# CCM_0025.net
KiCad netlist of a schematic drawn in EAGLE
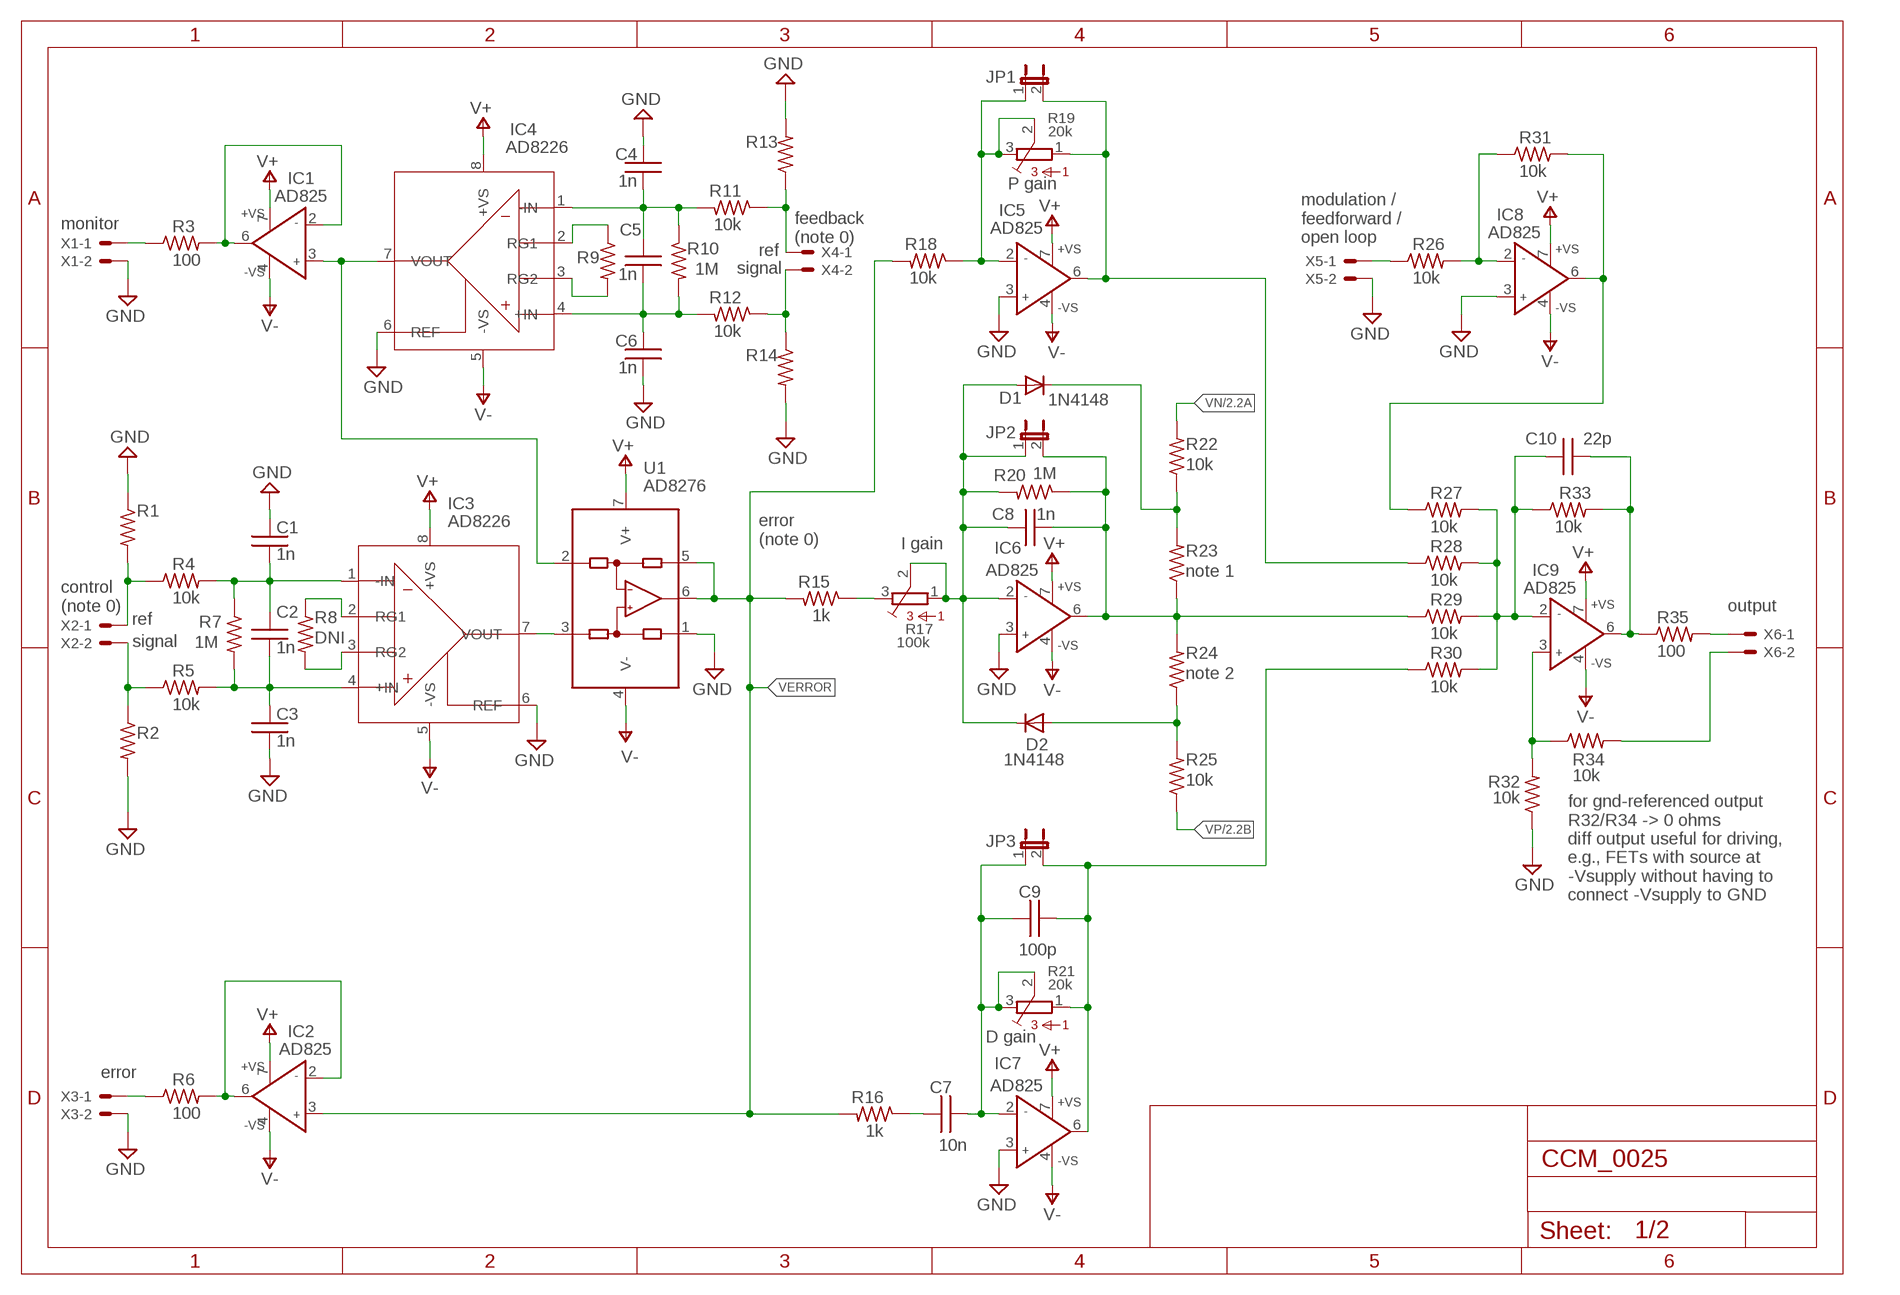
[diagram p0: schematic, sheet 1]
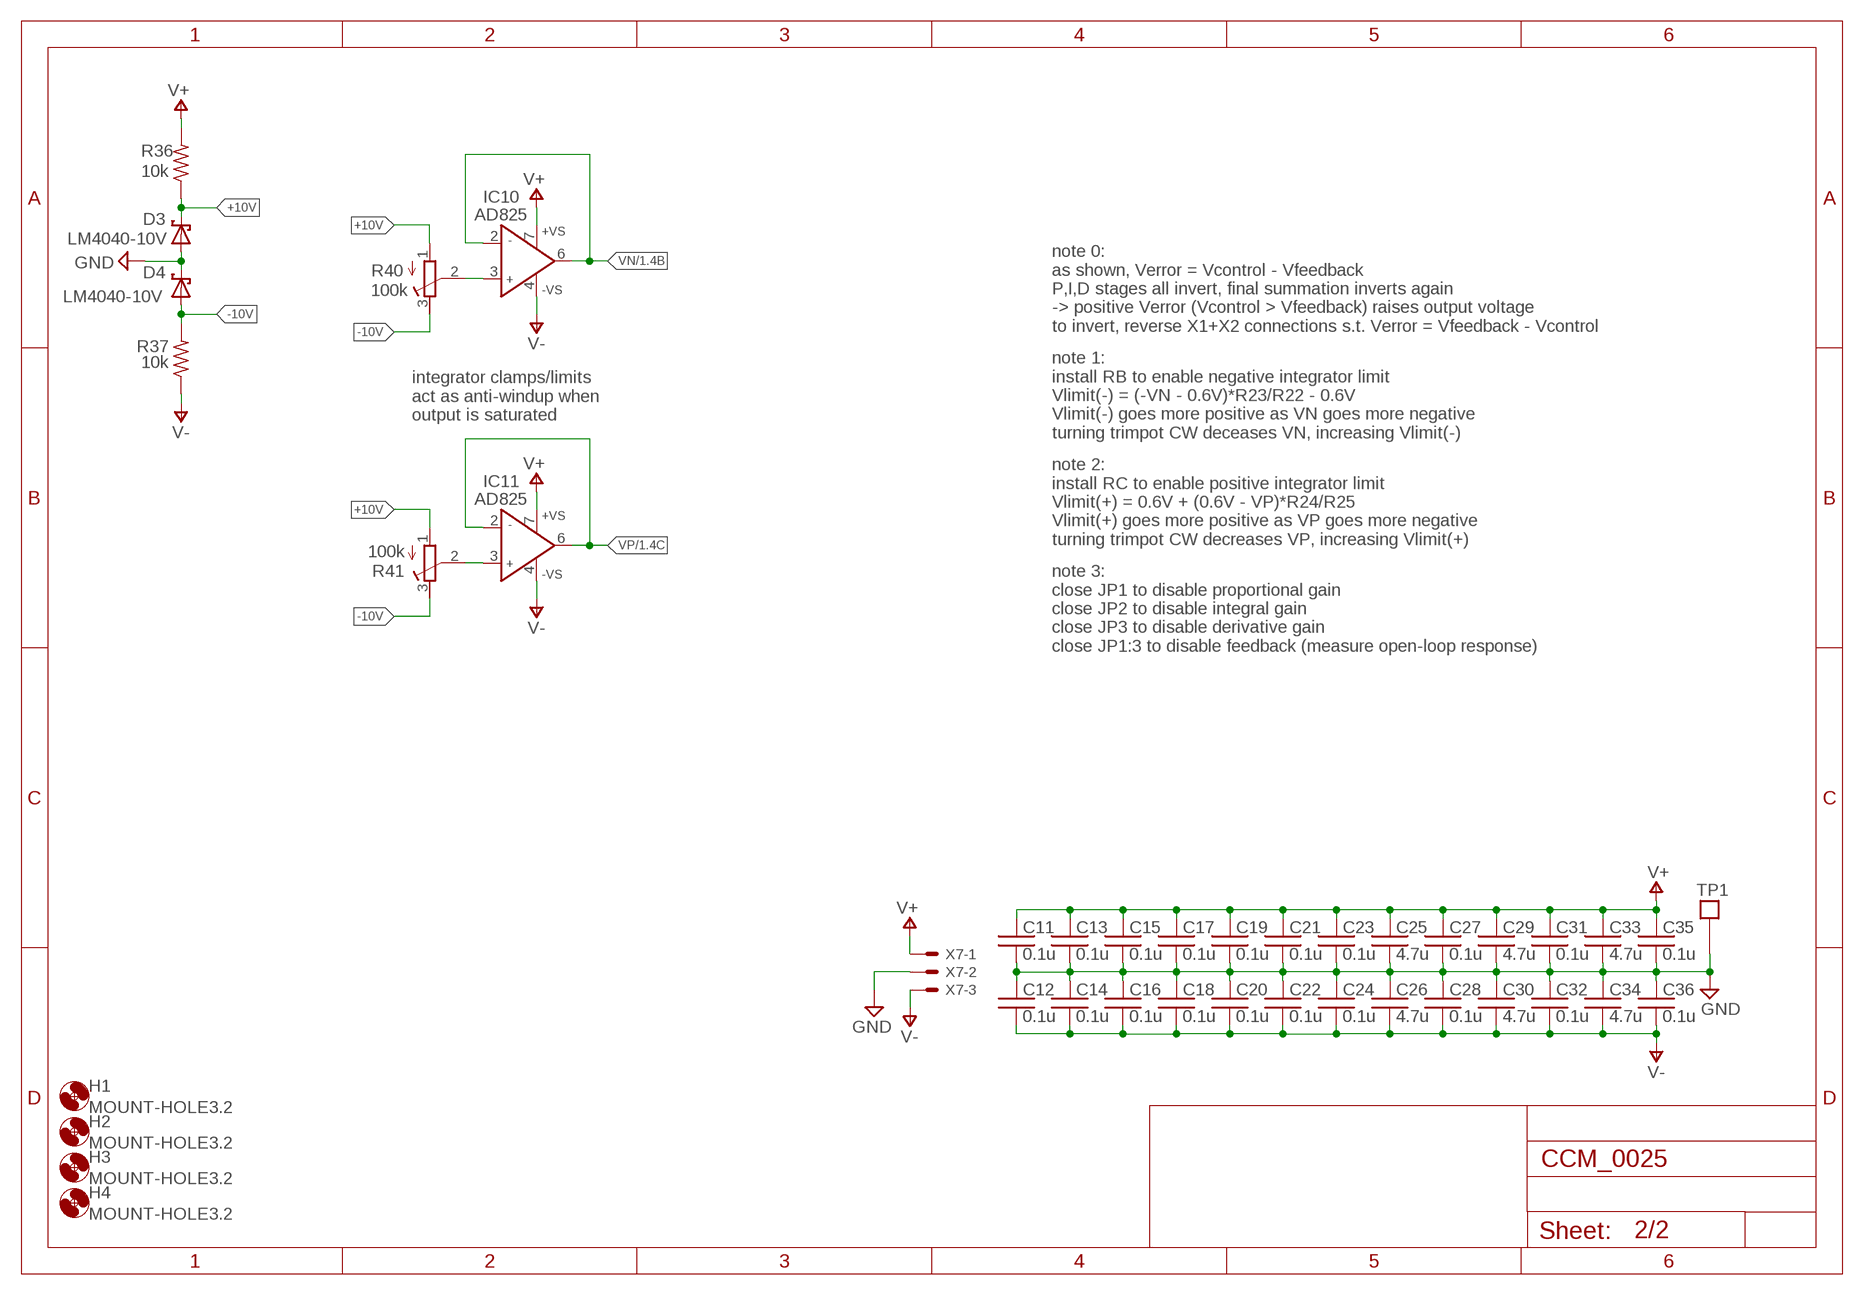
[diagram p1: schematic, sheet 2]

(export (version "E")
  (design (tool "Eeschema 10.0.6"))
  (components
    (comp (ref "C1")
      (value "1n")
      (footprint "eagle-import:0603")
      (libsource (lib "eagle-import") (part "C0603"))
    )
    (comp (ref "C2")
      (value "1n")
      (footprint "eagle-import:0603")
      (libsource (lib "eagle-import") (part "C0603"))
    )
    (comp (ref "C3")
      (value "1n")
      (footprint "eagle-import:0603")
      (libsource (lib "eagle-import") (part "C0603"))
    )
    (comp (ref "C4")
      (value "1n")
      (footprint "eagle-import:0603")
      (libsource (lib "eagle-import") (part "C0603"))
    )
    (comp (ref "C5")
      (value "1n")
      (footprint "eagle-import:0603")
      (libsource (lib "eagle-import") (part "C0603"))
    )
    (comp (ref "C6")
      (value "1n")
      (footprint "eagle-import:0603")
      (libsource (lib "eagle-import") (part "C0603"))
    )
    (comp (ref "C7")
      (value "10n")
      (footprint "eagle-import:0603")
      (libsource (lib "eagle-import") (part "C0603"))
    )
    (comp (ref "C8")
      (value "1n")
      (footprint "eagle-import:0603")
      (libsource (lib "eagle-import") (part "C0603"))
    )
    (comp (ref "C9")
      (value "100p")
      (footprint "eagle-import:0603")
      (libsource (lib "eagle-import") (part "C0603"))
    )
    (comp (ref "C10")
      (value "22p")
      (footprint "eagle-import:0603")
      (libsource (lib "eagle-import") (part "C0603"))
    )
    (comp (ref "D1")
      (value "1N4148")
      (footprint "eagle-import:SOD323_ST")
      (libsource (lib "eagle-import") (part "1N4148"))
    )
    (comp (ref "D2")
      (value "1N4148")
      (footprint "eagle-import:SOD323_ST")
      (libsource (lib "eagle-import") (part "1N4148"))
    )
    (comp (ref "IC1")
      (value "AD825")
      (footprint "eagle-import:SO8")
      (fields (field (name "MF") "ALTERA CORPORATION") (field (name "MPN") "AD825ARZ"))
      (libsource (lib "eagle-import") (part "AD825_BR"))
    )
    (comp (ref "IC2")
      (value "AD825")
      (footprint "eagle-import:SO8")
      (fields (field (name "MF") "ALTERA CORPORATION") (field (name "MPN") "AD825ARZ"))
      (libsource (lib "eagle-import") (part "AD825_BR"))
    )
    (comp (ref "IC3")
      (value "AD8226")
      (footprint "eagle-import:SO08")
      (libsource (lib "eagle-import") (part "AD8226"))
    )
    (comp (ref "IC4")
      (value "AD8226")
      (footprint "eagle-import:SO08")
      (libsource (lib "eagle-import") (part "AD8226"))
    )
    (comp (ref "IC5")
      (value "AD825")
      (footprint "eagle-import:SO8")
      (fields (field (name "MF") "ALTERA CORPORATION") (field (name "MPN") "AD825ARZ"))
      (libsource (lib "eagle-import") (part "AD825_BR"))
    )
    (comp (ref "IC6")
      (value "AD825")
      (footprint "eagle-import:SO8")
      (fields (field (name "MF") "ALTERA CORPORATION") (field (name "MPN") "AD825ARZ"))
      (libsource (lib "eagle-import") (part "AD825_BR"))
    )
    (comp (ref "IC7")
      (value "AD825")
      (footprint "eagle-import:SO8")
      (fields (field (name "MF") "ALTERA CORPORATION") (field (name "MPN") "AD825ARZ"))
      (libsource (lib "eagle-import") (part "AD825_BR"))
    )
    (comp (ref "IC8")
      (value "AD825")
      (footprint "eagle-import:SO8")
      (fields (field (name "MF") "ALTERA CORPORATION") (field (name "MPN") "AD825ARZ"))
      (libsource (lib "eagle-import") (part "AD825_BR"))
    )
    (comp (ref "IC9")
      (value "AD825")
      (footprint "eagle-import:SO8")
      (fields (field (name "MF") "ALTERA CORPORATION") (field (name "MPN") "AD825ARZ"))
      (libsource (lib "eagle-import") (part "AD825_BR"))
    )
    (comp (ref "JP1")
      (value "JP1E")
      (footprint "eagle-import:JP1")
      (libsource (lib "eagle-import") (part "JP1E"))
    )
    (comp (ref "JP2")
      (value "JP1E")
      (footprint "eagle-import:JP1")
      (libsource (lib "eagle-import") (part "JP1E"))
    )
    (comp (ref "JP3")
      (value "JP1E")
      (footprint "eagle-import:JP1")
      (libsource (lib "eagle-import") (part "JP1E"))
    )
    (comp (ref "R1")
      (value "10k")
      (footprint "eagle-import:0603")
      (libsource (lib "eagle-import") (part "R0603"))
    )
    (comp (ref "R2")
      (value "10k")
      (footprint "eagle-import:0603")
      (libsource (lib "eagle-import") (part "R0603"))
    )
    (comp (ref "R3")
      (value "100")
      (footprint "eagle-import:0603")
      (libsource (lib "eagle-import") (part "R0603"))
    )
    (comp (ref "R4")
      (value "10k")
      (footprint "eagle-import:0603")
      (libsource (lib "eagle-import") (part "R0603"))
    )
    (comp (ref "R5")
      (value "10k")
      (footprint "eagle-import:0603")
      (libsource (lib "eagle-import") (part "R0603"))
    )
    (comp (ref "R6")
      (value "100")
      (footprint "eagle-import:0603")
      (libsource (lib "eagle-import") (part "R0603"))
    )
    (comp (ref "R7")
      (value "1M")
      (footprint "eagle-import:0603")
      (libsource (lib "eagle-import") (part "R0603"))
    )
    (comp (ref "R8")
      (value "DNI")
      (footprint "eagle-import:0603")
      (libsource (lib "eagle-import") (part "R0603"))
    )
    (comp (ref "R9")
      (value "DNI")
      (footprint "eagle-import:0603")
      (libsource (lib "eagle-import") (part "R0603"))
    )
    (comp (ref "R10")
      (value "1M")
      (footprint "eagle-import:0603")
      (libsource (lib "eagle-import") (part "R0603"))
    )
    (comp (ref "R11")
      (value "10k")
      (footprint "eagle-import:0603")
      (libsource (lib "eagle-import") (part "R0603"))
    )
    (comp (ref "R12")
      (value "10k")
      (footprint "eagle-import:0603")
      (libsource (lib "eagle-import") (part "R0603"))
    )
    (comp (ref "R13")
      (value "10k")
      (footprint "eagle-import:0603")
      (libsource (lib "eagle-import") (part "R0603"))
    )
    (comp (ref "R14")
      (value "10k")
      (footprint "eagle-import:0603")
      (libsource (lib "eagle-import") (part "R0603"))
    )
    (comp (ref "R15")
      (value "1k")
      (footprint "eagle-import:0603")
      (libsource (lib "eagle-import") (part "R0603"))
    )
    (comp (ref "R16")
      (value "1k")
      (footprint "eagle-import:0603")
      (libsource (lib "eagle-import") (part "R0603"))
    )
    (comp (ref "R17")
      (value "100k")
      (footprint "eagle-import:3386C")
      (libsource (lib "eagle-import") (part "3386-C"))
    )
    (comp (ref "R18")
      (value "10k")
      (footprint "eagle-import:0603")
      (libsource (lib "eagle-import") (part "R0603"))
    )
    (comp (ref "R19")
      (value "20k")
      (footprint "eagle-import:3386C")
      (libsource (lib "eagle-import") (part "3386-C"))
    )
    (comp (ref "R20")
      (value "1M")
      (footprint "eagle-import:0603")
      (libsource (lib "eagle-import") (part "R0603"))
    )
    (comp (ref "R21")
      (value "20k")
      (footprint "eagle-import:3386C")
      (libsource (lib "eagle-import") (part "3386-C"))
    )
    (comp (ref "R22")
      (value "10k")
      (footprint "eagle-import:0603")
      (libsource (lib "eagle-import") (part "R0603"))
    )
    (comp (ref "R23")
      (value "note 1")
      (footprint "eagle-import:0603")
      (libsource (lib "eagle-import") (part "R0603"))
    )
    (comp (ref "R24")
      (value "note 2")
      (footprint "eagle-import:0603")
      (libsource (lib "eagle-import") (part "R0603"))
    )
    (comp (ref "R25")
      (value "10k")
      (footprint "eagle-import:0603")
      (libsource (lib "eagle-import") (part "R0603"))
    )
    (comp (ref "R26")
      (value "10k")
      (footprint "eagle-import:0603")
      (libsource (lib "eagle-import") (part "R0603"))
    )
    (comp (ref "R27")
      (value "10k")
      (footprint "eagle-import:0603")
      (libsource (lib "eagle-import") (part "R0603"))
    )
    (comp (ref "R28")
      (value "10k")
      (footprint "eagle-import:0603")
      (libsource (lib "eagle-import") (part "R0603"))
    )
    (comp (ref "R29")
      (value "10k")
      (footprint "eagle-import:0603")
      (libsource (lib "eagle-import") (part "R0603"))
    )
    (comp (ref "R30")
      (value "10k")
      (footprint "eagle-import:0603")
      (libsource (lib "eagle-import") (part "R0603"))
    )
    (comp (ref "R31")
      (value "10k")
      (footprint "eagle-import:0603")
      (libsource (lib "eagle-import") (part "R0603"))
    )
    (comp (ref "R32")
      (value "10k")
      (footprint "eagle-import:0603")
      (libsource (lib "eagle-import") (part "R0603"))
    )
    (comp (ref "R33")
      (value "10k")
      (footprint "eagle-import:0603")
      (libsource (lib "eagle-import") (part "R0603"))
    )
    (comp (ref "R34")
      (value "10k")
      (footprint "eagle-import:0603")
      (libsource (lib "eagle-import") (part "R0603"))
    )
    (comp (ref "R35")
      (value "100")
      (footprint "eagle-import:0603")
      (libsource (lib "eagle-import") (part "R0603"))
    )
    (comp (ref "U1")
      (value "AD8276")
      (footprint "eagle-import:SO8")
      (libsource (lib "eagle-import") (part "AD8276"))
    )
    (comp (ref "X1")
      (value "22-23-2021")
      (footprint "eagle-import:22-23-2021")
      (fields (field (name "MF") "MOLEX"))
      (libsource (lib "eagle-import") (part "22-23-2021"))
    )
    (comp (ref "X2")
      (value "22-23-2021")
      (footprint "eagle-import:22-23-2021")
      (fields (field (name "MF") "MOLEX"))
      (libsource (lib "eagle-import") (part "22-23-2021"))
    )
    (comp (ref "X3")
      (value "22-23-2021")
      (footprint "eagle-import:22-23-2021")
      (fields (field (name "MF") "MOLEX"))
      (libsource (lib "eagle-import") (part "22-23-2021"))
    )
    (comp (ref "X4")
      (value "22-23-2021")
      (footprint "eagle-import:22-23-2021")
      (fields (field (name "MF") "MOLEX"))
      (libsource (lib "eagle-import") (part "22-23-2021"))
    )
    (comp (ref "X5")
      (value "22-23-2021")
      (footprint "eagle-import:22-23-2021")
      (fields (field (name "MF") "MOLEX"))
      (libsource (lib "eagle-import") (part "22-23-2021"))
    )
    (comp (ref "X6")
      (value "22-23-2021")
      (footprint "eagle-import:22-23-2021")
      (fields (field (name "MF") "MOLEX"))
      (libsource (lib "eagle-import") (part "22-23-2021"))
    )
    (comp (ref "C11")
      (value "0.1u")
      (footprint "eagle-import:0603")
      (libsource (lib "eagle-import") (part "C0603"))
    )
    (comp (ref "C12")
      (value "0.1u")
      (footprint "eagle-import:0603")
      (libsource (lib "eagle-import") (part "C0603"))
    )
    (comp (ref "C13")
      (value "0.1u")
      (footprint "eagle-import:0603")
      (libsource (lib "eagle-import") (part "C0603"))
    )
    (comp (ref "C14")
      (value "0.1u")
      (footprint "eagle-import:0603")
      (libsource (lib "eagle-import") (part "C0603"))
    )
    (comp (ref "C15")
      (value "0.1u")
      (footprint "eagle-import:0603")
      (libsource (lib "eagle-import") (part "C0603"))
    )
    (comp (ref "C16")
      (value "0.1u")
      (footprint "eagle-import:0603")
      (libsource (lib "eagle-import") (part "C0603"))
    )
    (comp (ref "C17")
      (value "0.1u")
      (footprint "eagle-import:0603")
      (libsource (lib "eagle-import") (part "C0603"))
    )
    (comp (ref "C18")
      (value "0.1u")
      (footprint "eagle-import:0603")
      (libsource (lib "eagle-import") (part "C0603"))
    )
    (comp (ref "C19")
      (value "0.1u")
      (footprint "eagle-import:0603")
      (libsource (lib "eagle-import") (part "C0603"))
    )
    (comp (ref "C20")
      (value "0.1u")
      (footprint "eagle-import:0603")
      (libsource (lib "eagle-import") (part "C0603"))
    )
    (comp (ref "C21")
      (value "0.1u")
      (footprint "eagle-import:0603")
      (libsource (lib "eagle-import") (part "C0603"))
    )
    (comp (ref "C22")
      (value "0.1u")
      (footprint "eagle-import:0603")
      (libsource (lib "eagle-import") (part "C0603"))
    )
    (comp (ref "C23")
      (value "0.1u")
      (footprint "eagle-import:0603")
      (libsource (lib "eagle-import") (part "C0603"))
    )
    (comp (ref "C24")
      (value "0.1u")
      (footprint "eagle-import:0603")
      (libsource (lib "eagle-import") (part "C0603"))
    )
    (comp (ref "C25")
      (value "4.7u")
      (footprint "eagle-import:0603")
      (libsource (lib "eagle-import") (part "C0603"))
    )
    (comp (ref "C26")
      (value "4.7u")
      (footprint "eagle-import:0603")
      (libsource (lib "eagle-import") (part "C0603"))
    )
    (comp (ref "C27")
      (value "0.1u")
      (footprint "eagle-import:0603")
      (libsource (lib "eagle-import") (part "C0603"))
    )
    (comp (ref "C28")
      (value "0.1u")
      (footprint "eagle-import:0603")
      (libsource (lib "eagle-import") (part "C0603"))
    )
    (comp (ref "C29")
      (value "4.7u")
      (footprint "eagle-import:0603")
      (libsource (lib "eagle-import") (part "C0603"))
    )
    (comp (ref "C30")
      (value "4.7u")
      (footprint "eagle-import:0603")
      (libsource (lib "eagle-import") (part "C0603"))
    )
    (comp (ref "C31")
      (value "0.1u")
      (footprint "eagle-import:0603")
      (libsource (lib "eagle-import") (part "C0603"))
    )
    (comp (ref "C32")
      (value "0.1u")
      (footprint "eagle-import:0603")
      (libsource (lib "eagle-import") (part "C0603"))
    )
    (comp (ref "C33")
      (value "4.7u")
      (footprint "eagle-import:0603")
      (libsource (lib "eagle-import") (part "C0603"))
    )
    (comp (ref "C34")
      (value "4.7u")
      (footprint "eagle-import:0603")
      (libsource (lib "eagle-import") (part "C0603"))
    )
    (comp (ref "C35")
      (value "0.1u")
      (footprint "eagle-import:0603")
      (libsource (lib "eagle-import") (part "C0603"))
    )
    (comp (ref "C36")
      (value "0.1u")
      (footprint "eagle-import:0603")
      (libsource (lib "eagle-import") (part "C0603"))
    )
    (comp (ref "D3")
      (value "LM4040-10V")
      (footprint "eagle-import:SOT23")
      (libsource (lib "eagle-import") (part "LM4040"))
    )
    (comp (ref "D4")
      (value "LM4040-10V")
      (footprint "eagle-import:SOT23")
      (libsource (lib "eagle-import") (part "LM4040"))
    )
    (comp (ref "H1")
      (value "MOUNT-HOLE3.2")
      (footprint "eagle-import:3,2")
      (libsource (lib "eagle-import") (part "MOUNT-HOLE3.2"))
    )
    (comp (ref "H2")
      (value "MOUNT-HOLE3.2")
      (footprint "eagle-import:3,2")
      (libsource (lib "eagle-import") (part "MOUNT-HOLE3.2"))
    )
    (comp (ref "H3")
      (value "MOUNT-HOLE3.2")
      (footprint "eagle-import:3,2")
      (libsource (lib "eagle-import") (part "MOUNT-HOLE3.2"))
    )
    (comp (ref "H4")
      (value "MOUNT-HOLE3.2")
      (footprint "eagle-import:3,2")
      (libsource (lib "eagle-import") (part "MOUNT-HOLE3.2"))
    )
    (comp (ref "IC10")
      (value "AD825")
      (footprint "eagle-import:SO8")
      (fields (field (name "MF") "ALTERA CORPORATION") (field (name "MPN") "AD825ARZ"))
      (libsource (lib "eagle-import") (part "AD825_BR"))
    )
    (comp (ref "IC11")
      (value "AD825")
      (footprint "eagle-import:SO8")
      (fields (field (name "MF") "ALTERA CORPORATION") (field (name "MPN") "AD825ARZ"))
      (libsource (lib "eagle-import") (part "AD825_BR"))
    )
    (comp (ref "R36")
      (value "10k")
      (footprint "eagle-import:0603")
      (libsource (lib "eagle-import") (part "R0603"))
    )
    (comp (ref "R37")
      (value "10k")
      (footprint "eagle-import:0603")
      (libsource (lib "eagle-import") (part "R0603"))
    )
    (comp (ref "R40")
      (value "100k")
      (footprint "eagle-import:RTRIM3296W")
      (libsource (lib "eagle-import") (part "R-TRIMM3296W"))
    )
    (comp (ref "R41")
      (value "100k")
      (footprint "eagle-import:RTRIM3296W")
      (libsource (lib "eagle-import") (part "R-TRIMM3296W"))
    )
    (comp (ref "TP1")
      (value "TESTPOINT")
      (footprint "eagle-import:TESTPOINT")
      (libsource (lib "eagle-import") (part "TESTPOINT"))
    )
    (comp (ref "X7")
      (value "22-23-2031")
      (footprint "eagle-import:22-23-2031")
      (fields (field (name "MF") "MOLEX"))
      (libsource (lib "eagle-import") (part "22-23-2031"))
    )
  )
  (nets
    (net (code "1") (name "+10V") (class "Default")
      (node (ref "D3") (pin "1") (pinfunction "C_1") (pintype "passive"))
      (node (ref "R36") (pin "1") (pinfunction "1_1") (pintype "passive"))
      (node (ref "R40") (pin "1") (pinfunction "A_1") (pintype "passive"))
      (node (ref "R41") (pin "1") (pinfunction "A_1") (pintype "passive"))
    )
    (net (code "2") (name "-10V") (class "Default")
      (node (ref "D4") (pin "2") (pinfunction "A_2") (pintype "passive"))
      (node (ref "R37") (pin "2") (pinfunction "2_2") (pintype "passive"))
      (node (ref "R40") (pin "3") (pinfunction "E_3") (pintype "passive"))
      (node (ref "R41") (pin "3") (pinfunction "E_3") (pintype "passive"))
    )
    (net (code "3") (name "GND") (class "Default")
      (node (ref "C1") (pin "1") (pinfunction "1_1") (pintype "passive"))
      (node (ref "C11") (pin "2") (pinfunction "2_2") (pintype "passive"))
      (node (ref "C12") (pin "1") (pinfunction "1_1") (pintype "passive"))
      (node (ref "C13") (pin "2") (pinfunction "2_2") (pintype "passive"))
      (node (ref "C14") (pin "1") (pinfunction "1_1") (pintype "passive"))
      (node (ref "C15") (pin "2") (pinfunction "2_2") (pintype "passive"))
      (node (ref "C16") (pin "1") (pinfunction "1_1") (pintype "passive"))
      (node (ref "C17") (pin "2") (pinfunction "2_2") (pintype "passive"))
      (node (ref "C18") (pin "1") (pinfunction "1_1") (pintype "passive"))
      (node (ref "C19") (pin "2") (pinfunction "2_2") (pintype "passive"))
      (node (ref "C20") (pin "1") (pinfunction "1_1") (pintype "passive"))
      (node (ref "C21") (pin "2") (pinfunction "2_2") (pintype "passive"))
      (node (ref "C22") (pin "1") (pinfunction "1_1") (pintype "passive"))
      (node (ref "C23") (pin "2") (pinfunction "2_2") (pintype "passive"))
      (node (ref "C24") (pin "1") (pinfunction "1_1") (pintype "passive"))
      (node (ref "C25") (pin "2") (pinfunction "2_2") (pintype "passive"))
      (node (ref "C26") (pin "1") (pinfunction "1_1") (pintype "passive"))
      (node (ref "C27") (pin "2") (pinfunction "2_2") (pintype "passive"))
      (node (ref "C28") (pin "1") (pinfunction "1_1") (pintype "passive"))
      (node (ref "C29") (pin "2") (pinfunction "2_2") (pintype "passive"))
      (node (ref "C3") (pin "2") (pinfunction "2_2") (pintype "passive"))
      (node (ref "C30") (pin "1") (pinfunction "1_1") (pintype "passive"))
      (node (ref "C31") (pin "2") (pinfunction "2_2") (pintype "passive"))
      (node (ref "C32") (pin "1") (pinfunction "1_1") (pintype "passive"))
      (node (ref "C33") (pin "2") (pinfunction "2_2") (pintype "passive"))
      (node (ref "C34") (pin "1") (pinfunction "1_1") (pintype "passive"))
      (node (ref "C35") (pin "2") (pinfunction "2_2") (pintype "passive"))
      (node (ref "C36") (pin "1") (pinfunction "1_1") (pintype "passive"))
      (node (ref "C4") (pin "1") (pinfunction "1_1") (pintype "passive"))
      (node (ref "C6") (pin "2") (pinfunction "2_2") (pintype "passive"))
      (node (ref "D3") (pin "2") (pinfunction "A_2") (pintype "passive"))
      (node (ref "D4") (pin "1") (pinfunction "C_1") (pintype "passive"))
      (node (ref "IC3") (pin "6") (pinfunction "REF_6") (pintype "bidirectional"))
      (node (ref "IC4") (pin "6") (pinfunction "REF_6") (pintype "bidirectional"))
      (node (ref "IC5") (pin "3") (pinfunction "IN+_3") (pintype "input"))
      (node (ref "IC6") (pin "3") (pinfunction "IN+_3") (pintype "input"))
      (node (ref "IC7") (pin "3") (pinfunction "IN+_3") (pintype "input"))
      (node (ref "IC8") (pin "3") (pinfunction "IN+_3") (pintype "input"))
      (node (ref "R1") (pin "1") (pinfunction "1_1") (pintype "passive"))
      (node (ref "R13") (pin "2") (pinfunction "2_2") (pintype "passive"))
      (node (ref "R14") (pin "2") (pinfunction "2_2") (pintype "passive"))
      (node (ref "R2") (pin "2") (pinfunction "2_2") (pintype "passive"))
      (node (ref "R32") (pin "1") (pinfunction "1_1") (pintype "passive"))
      (node (ref "TP1") (pin "P$1") (pinfunction "P$1_P$1") (pintype "bidirectional"))
      (node (ref "U1") (pin "1") (pinfunction "REF_1") (pintype "passive"))
      (node (ref "X1") (pin "2") (pinfunction "S_2") (pintype "passive"))
      (node (ref "X3") (pin "2") (pinfunction "S_2") (pintype "passive"))
      (node (ref "X5") (pin "2") (pinfunction "S_2") (pintype "passive"))
      (node (ref "X7") (pin "2") (pinfunction "S_2") (pintype "passive"))
    )
    (net (code "4") (name "Net-(C7-Pad2)") (class "Default")
      (node (ref "C7") (pin "2") (pinfunction "2_2") (pintype "passive"))
      (node (ref "R16") (pin "1") (pinfunction "1_1") (pintype "passive"))
    )
    (net (code "5") (name "Net-(D1-PadC)") (class "Default")
      (node (ref "D1") (pin "C") (pinfunction "C_C") (pintype "passive"))
      (node (ref "R22") (pin "1") (pinfunction "1_1") (pintype "passive"))
      (node (ref "R23") (pin "2") (pinfunction "2_2") (pintype "passive"))
    )
    (net (code "6") (name "Net-(D2-PadA)") (class "Default")
      (node (ref "D2") (pin "A") (pinfunction "A_A") (pintype "passive"))
      (node (ref "R24") (pin "1") (pinfunction "1_1") (pintype "passive"))
      (node (ref "R25") (pin "2") (pinfunction "2_2") (pintype "passive"))
    )
    (net (code "7") (name "Net-(IC1-IN+)") (class "Default")
      (node (ref "IC1") (pin "3") (pinfunction "IN+_3") (pintype "input"))
      (node (ref "IC4") (pin "7") (pinfunction "VOUT_7") (pintype "bidirectional"))
      (node (ref "U1") (pin "2") (pinfunction "-IN_2") (pintype "input"))
    )
    (net (code "8") (name "Net-(IC1-IN-)") (class "Default")
      (node (ref "IC1") (pin "2") (pinfunction "IN-_2") (pintype "input"))
      (node (ref "IC1") (pin "6") (pinfunction "OUT_6") (pintype "output"))
      (node (ref "R3") (pin "2") (pinfunction "2_2") (pintype "passive"))
    )
    (net (code "9") (name "Net-(IC2-IN-)") (class "Default")
      (node (ref "IC2") (pin "2") (pinfunction "IN-_2") (pintype "input"))
      (node (ref "IC2") (pin "6") (pinfunction "OUT_6") (pintype "output"))
      (node (ref "R6") (pin "2") (pinfunction "2_2") (pintype "passive"))
    )
    (net (code "10") (name "Net-(IC3-+IN)") (class "Default")
      (node (ref "C2") (pin "2") (pinfunction "2_2") (pintype "passive"))
      (node (ref "C3") (pin "1") (pinfunction "1_1") (pintype "passive"))
      (node (ref "IC3") (pin "4") (pinfunction "+IN_4") (pintype "bidirectional"))
      (node (ref "R5") (pin "2") (pinfunction "2_2") (pintype "passive"))
      (node (ref "R7") (pin "2") (pinfunction "2_2") (pintype "passive"))
    )
    (net (code "11") (name "Net-(IC3--IN)") (class "Default")
      (node (ref "C1") (pin "2") (pinfunction "2_2") (pintype "passive"))
      (node (ref "C2") (pin "1") (pinfunction "1_1") (pintype "passive"))
      (node (ref "IC3") (pin "1") (pinfunction "-IN_1") (pintype "bidirectional"))
      (node (ref "R4") (pin "2") (pinfunction "2_2") (pintype "passive"))
      (node (ref "R7") (pin "1") (pinfunction "1_1") (pintype "passive"))
    )
    (net (code "12") (name "Net-(IC3-RG1)") (class "Default")
      (node (ref "IC3") (pin "2") (pinfunction "RG1_2") (pintype "bidirectional"))
      (node (ref "R8") (pin "1") (pinfunction "1_1") (pintype "passive"))
    )
    (net (code "13") (name "Net-(IC3-RG2)") (class "Default")
      (node (ref "IC3") (pin "3") (pinfunction "RG2_3") (pintype "bidirectional"))
      (node (ref "R8") (pin "2") (pinfunction "2_2") (pintype "passive"))
    )
    (net (code "14") (name "Net-(IC3-VOUT)") (class "Default")
      (node (ref "IC3") (pin "7") (pinfunction "VOUT_7") (pintype "bidirectional"))
      (node (ref "U1") (pin "3") (pinfunction "+IN_3") (pintype "input"))
    )
    (net (code "15") (name "Net-(IC4-+IN)") (class "Default")
      (node (ref "C5") (pin "2") (pinfunction "2_2") (pintype "passive"))
      (node (ref "C6") (pin "1") (pinfunction "1_1") (pintype "passive"))
      (node (ref "IC4") (pin "4") (pinfunction "+IN_4") (pintype "bidirectional"))
      (node (ref "R10") (pin "2") (pinfunction "2_2") (pintype "passive"))
      (node (ref "R12") (pin "2") (pinfunction "2_2") (pintype "passive"))
    )
    (net (code "16") (name "Net-(IC4--IN)") (class "Default")
      (node (ref "C4") (pin "2") (pinfunction "2_2") (pintype "passive"))
      (node (ref "C5") (pin "1") (pinfunction "1_1") (pintype "passive"))
      (node (ref "IC4") (pin "1") (pinfunction "-IN_1") (pintype "bidirectional"))
      (node (ref "R10") (pin "1") (pinfunction "1_1") (pintype "passive"))
      (node (ref "R11") (pin "2") (pinfunction "2_2") (pintype "passive"))
    )
    (net (code "17") (name "Net-(IC4-RG1)") (class "Default")
      (node (ref "IC4") (pin "2") (pinfunction "RG1_2") (pintype "bidirectional"))
      (node (ref "R9") (pin "1") (pinfunction "1_1") (pintype "passive"))
    )
    (net (code "18") (name "Net-(IC4-RG2)") (class "Default")
      (node (ref "IC4") (pin "3") (pinfunction "RG2_3") (pintype "bidirectional"))
      (node (ref "R9") (pin "2") (pinfunction "2_2") (pintype "passive"))
    )
    (net (code "19") (name "Net-(IC5-IN-)") (class "Default")
      (node (ref "IC5") (pin "2") (pinfunction "IN-_2") (pintype "input"))
      (node (ref "JP1") (pin "1") (pinfunction "1_1") (pintype "passive"))
      (node (ref "R18") (pin "1") (pinfunction "1_1") (pintype "passive"))
      (node (ref "R19") (pin "2") (pinfunction "2_2") (pintype "passive"))
      (node (ref "R19") (pin "3") (pinfunction "3_3") (pintype "passive"))
    )
    (net (code "20") (name "Net-(IC5-OUT)") (class "Default")
      (node (ref "IC5") (pin "6") (pinfunction "OUT_6") (pintype "output"))
      (node (ref "JP1") (pin "2") (pinfunction "2_2") (pintype "passive"))
      (node (ref "R19") (pin "1") (pinfunction "1_1") (pintype "passive"))
      (node (ref "R28") (pin "1") (pinfunction "1_1") (pintype "passive"))
    )
    (net (code "21") (name "Net-(IC6-IN-)") (class "Default")
      (node (ref "C8") (pin "2") (pinfunction "2_2") (pintype "passive"))
      (node (ref "D1") (pin "A") (pinfunction "A_A") (pintype "passive"))
      (node (ref "D2") (pin "C") (pinfunction "C_C") (pintype "passive"))
      (node (ref "IC6") (pin "2") (pinfunction "IN-_2") (pintype "input"))
      (node (ref "JP2") (pin "1") (pinfunction "1_1") (pintype "passive"))
      (node (ref "R17") (pin "1") (pinfunction "1_1") (pintype "passive"))
      (node (ref "R17") (pin "2") (pinfunction "2_2") (pintype "passive"))
      (node (ref "R20") (pin "2") (pinfunction "2_2") (pintype "passive"))
    )
    (net (code "22") (name "Net-(IC6-OUT)") (class "Default")
      (node (ref "C8") (pin "1") (pinfunction "1_1") (pintype "passive"))
      (node (ref "IC6") (pin "6") (pinfunction "OUT_6") (pintype "output"))
      (node (ref "JP2") (pin "2") (pinfunction "2_2") (pintype "passive"))
      (node (ref "R20") (pin "1") (pinfunction "1_1") (pintype "passive"))
      (node (ref "R23") (pin "1") (pinfunction "1_1") (pintype "passive"))
      (node (ref "R24") (pin "2") (pinfunction "2_2") (pintype "passive"))
      (node (ref "R29") (pin "1") (pinfunction "1_1") (pintype "passive"))
    )
    (net (code "23") (name "Net-(IC7-IN-)") (class "Default")
      (node (ref "C7") (pin "1") (pinfunction "1_1") (pintype "passive"))
      (node (ref "C9") (pin "2") (pinfunction "2_2") (pintype "passive"))
      (node (ref "IC7") (pin "2") (pinfunction "IN-_2") (pintype "input"))
      (node (ref "JP3") (pin "1") (pinfunction "1_1") (pintype "passive"))
      (node (ref "R21") (pin "2") (pinfunction "2_2") (pintype "passive"))
      (node (ref "R21") (pin "3") (pinfunction "3_3") (pintype "passive"))
    )
    (net (code "24") (name "Net-(IC7-OUT)") (class "Default")
      (node (ref "C9") (pin "1") (pinfunction "1_1") (pintype "passive"))
      (node (ref "IC7") (pin "6") (pinfunction "OUT_6") (pintype "output"))
      (node (ref "JP3") (pin "2") (pinfunction "2_2") (pintype "passive"))
      (node (ref "R21") (pin "1") (pinfunction "1_1") (pintype "passive"))
      (node (ref "R30") (pin "1") (pinfunction "1_1") (pintype "passive"))
    )
    (net (code "25") (name "Net-(IC8-IN-)") (class "Default")
      (node (ref "IC8") (pin "2") (pinfunction "IN-_2") (pintype "input"))
      (node (ref "R26") (pin "2") (pinfunction "2_2") (pintype "passive"))
      (node (ref "R31") (pin "1") (pinfunction "1_1") (pintype "passive"))
    )
    (net (code "26") (name "Net-(IC8-OUT)") (class "Default")
      (node (ref "IC8") (pin "6") (pinfunction "OUT_6") (pintype "output"))
      (node (ref "R27") (pin "1") (pinfunction "1_1") (pintype "passive"))
      (node (ref "R31") (pin "2") (pinfunction "2_2") (pintype "passive"))
    )
    (net (code "27") (name "Net-(IC9-IN+)") (class "Default")
      (node (ref "IC9") (pin "3") (pinfunction "IN+_3") (pintype "input"))
      (node (ref "R32") (pin "2") (pinfunction "2_2") (pintype "passive"))
      (node (ref "R34") (pin "1") (pinfunction "1_1") (pintype "passive"))
    )
    (net (code "28") (name "Net-(IC9-IN-)") (class "Default")
      (node (ref "C10") (pin "2") (pinfunction "2_2") (pintype "passive"))
      (node (ref "IC9") (pin "2") (pinfunction "IN-_2") (pintype "input"))
      (node (ref "R27") (pin "2") (pinfunction "2_2") (pintype "passive"))
      (node (ref "R28") (pin "2") (pinfunction "2_2") (pintype "passive"))
      (node (ref "R29") (pin "2") (pinfunction "2_2") (pintype "passive"))
      (node (ref "R30") (pin "2") (pinfunction "2_2") (pintype "passive"))
      (node (ref "R33") (pin "1") (pinfunction "1_1") (pintype "passive"))
    )
    (net (code "29") (name "Net-(IC9-OUT)") (class "Default")
      (node (ref "C10") (pin "1") (pinfunction "1_1") (pintype "passive"))
      (node (ref "IC9") (pin "6") (pinfunction "OUT_6") (pintype "output"))
      (node (ref "R33") (pin "2") (pinfunction "2_2") (pintype "passive"))
      (node (ref "R35") (pin "1") (pinfunction "1_1") (pintype "passive"))
    )
    (net (code "30") (name "Net-(IC10-IN+)") (class "Default")
      (node (ref "IC10") (pin "3") (pinfunction "IN+_3") (pintype "input"))
      (node (ref "R40") (pin "2") (pinfunction "S_2") (pintype "passive"))
    )
    (net (code "31") (name "Net-(IC11-IN+)") (class "Default")
      (node (ref "IC11") (pin "3") (pinfunction "IN+_3") (pintype "input"))
      (node (ref "R41") (pin "2") (pinfunction "S_2") (pintype "passive"))
    )
    (net (code "32") (name "Net-(R15-Pad1)") (class "Default")
      (node (ref "R15") (pin "1") (pinfunction "1_1") (pintype "passive"))
      (node (ref "R17") (pin "3") (pinfunction "3_3") (pintype "passive"))
    )
    (net (code "33") (name "Net-(X1A-S)") (class "Default")
      (node (ref "R3") (pin "1") (pinfunction "1_1") (pintype "passive"))
      (node (ref "X1") (pin "1") (pinfunction "S_1") (pintype "passive"))
    )
    (net (code "34") (name "Net-(X2A-S)") (class "Default")
      (node (ref "R1") (pin "2") (pinfunction "2_2") (pintype "passive"))
      (node (ref "R4") (pin "1") (pinfunction "1_1") (pintype "passive"))
      (node (ref "X2") (pin "1") (pinfunction "S_1") (pintype "passive"))
    )
    (net (code "35") (name "Net-(X2B-S)") (class "Default")
      (node (ref "R2") (pin "1") (pinfunction "1_1") (pintype "passive"))
      (node (ref "R5") (pin "1") (pinfunction "1_1") (pintype "passive"))
      (node (ref "X2") (pin "2") (pinfunction "S_2") (pintype "passive"))
    )
    (net (code "36") (name "Net-(X3A-S)") (class "Default")
      (node (ref "R6") (pin "1") (pinfunction "1_1") (pintype "passive"))
      (node (ref "X3") (pin "1") (pinfunction "S_1") (pintype "passive"))
    )
    (net (code "37") (name "Net-(X4A-S)") (class "Default")
      (node (ref "R11") (pin "1") (pinfunction "1_1") (pintype "passive"))
      (node (ref "R13") (pin "1") (pinfunction "1_1") (pintype "passive"))
      (node (ref "X4") (pin "1") (pinfunction "S_1") (pintype "passive"))
    )
    (net (code "38") (name "Net-(X4B-S)") (class "Default")
      (node (ref "R12") (pin "1") (pinfunction "1_1") (pintype "passive"))
      (node (ref "R14") (pin "1") (pinfunction "1_1") (pintype "passive"))
      (node (ref "X4") (pin "2") (pinfunction "S_2") (pintype "passive"))
    )
    (net (code "39") (name "Net-(X5A-S)") (class "Default")
      (node (ref "R26") (pin "1") (pinfunction "1_1") (pintype "passive"))
      (node (ref "X5") (pin "1") (pinfunction "S_1") (pintype "passive"))
    )
    (net (code "40") (name "Net-(X6A-S)") (class "Default")
      (node (ref "R35") (pin "2") (pinfunction "2_2") (pintype "passive"))
      (node (ref "X6") (pin "1") (pinfunction "S_1") (pintype "passive"))
    )
    (net (code "41") (name "Net-(X6B-S)") (class "Default")
      (node (ref "R34") (pin "2") (pinfunction "2_2") (pintype "passive"))
      (node (ref "X6") (pin "2") (pinfunction "S_2") (pintype "passive"))
    )
    (net (code "42") (name "V+") (class "Default")
      (node (ref "C11") (pin "1") (pinfunction "1_1") (pintype "passive"))
      (node (ref "C13") (pin "1") (pinfunction "1_1") (pintype "passive"))
      (node (ref "C15") (pin "1") (pinfunction "1_1") (pintype "passive"))
      (node (ref "C17") (pin "1") (pinfunction "1_1") (pintype "passive"))
      (node (ref "C19") (pin "1") (pinfunction "1_1") (pintype "passive"))
      (node (ref "C21") (pin "1") (pinfunction "1_1") (pintype "passive"))
      (node (ref "C23") (pin "1") (pinfunction "1_1") (pintype "passive"))
      (node (ref "C25") (pin "1") (pinfunction "1_1") (pintype "passive"))
      (node (ref "C27") (pin "1") (pinfunction "1_1") (pintype "passive"))
      (node (ref "C29") (pin "1") (pinfunction "1_1") (pintype "passive"))
      (node (ref "C31") (pin "1") (pinfunction "1_1") (pintype "passive"))
      (node (ref "C33") (pin "1") (pinfunction "1_1") (pintype "passive"))
      (node (ref "C35") (pin "1") (pinfunction "1_1") (pintype "passive"))
      (node (ref "IC1") (pin "7") (pinfunction "+VS_7") (pintype "input"))
      (node (ref "IC10") (pin "7") (pinfunction "+VS_7") (pintype "input"))
      (node (ref "IC11") (pin "7") (pinfunction "+VS_7") (pintype "input"))
      (node (ref "IC2") (pin "7") (pinfunction "+VS_7") (pintype "input"))
      (node (ref "IC3") (pin "8") (pinfunction "+VS_8") (pintype "bidirectional"))
      (node (ref "IC4") (pin "8") (pinfunction "+VS_8") (pintype "bidirectional"))
      (node (ref "IC5") (pin "7") (pinfunction "+VS_7") (pintype "input"))
      (node (ref "IC6") (pin "7") (pinfunction "+VS_7") (pintype "input"))
      (node (ref "IC7") (pin "7") (pinfunction "+VS_7") (pintype "input"))
      (node (ref "IC8") (pin "7") (pinfunction "+VS_7") (pintype "input"))
      (node (ref "IC9") (pin "7") (pinfunction "+VS_7") (pintype "input"))
      (node (ref "R36") (pin "2") (pinfunction "2_2") (pintype "passive"))
      (node (ref "U1") (pin "7") (pinfunction "V+_7") (pintype "power_in"))
      (node (ref "X7") (pin "1") (pinfunction "S_1") (pintype "passive"))
    )
    (net (code "43") (name "V-") (class "Default")
      (node (ref "C12") (pin "2") (pinfunction "2_2") (pintype "passive"))
      (node (ref "C14") (pin "2") (pinfunction "2_2") (pintype "passive"))
      (node (ref "C16") (pin "2") (pinfunction "2_2") (pintype "passive"))
      (node (ref "C18") (pin "2") (pinfunction "2_2") (pintype "passive"))
      (node (ref "C20") (pin "2") (pinfunction "2_2") (pintype "passive"))
      (node (ref "C22") (pin "2") (pinfunction "2_2") (pintype "passive"))
      (node (ref "C24") (pin "2") (pinfunction "2_2") (pintype "passive"))
      (node (ref "C26") (pin "2") (pinfunction "2_2") (pintype "passive"))
      (node (ref "C28") (pin "2") (pinfunction "2_2") (pintype "passive"))
      (node (ref "C30") (pin "2") (pinfunction "2_2") (pintype "passive"))
      (node (ref "C32") (pin "2") (pinfunction "2_2") (pintype "passive"))
      (node (ref "C34") (pin "2") (pinfunction "2_2") (pintype "passive"))
      (node (ref "C36") (pin "2") (pinfunction "2_2") (pintype "passive"))
      (node (ref "IC1") (pin "4") (pinfunction "-VS_4") (pintype "input"))
      (node (ref "IC10") (pin "4") (pinfunction "-VS_4") (pintype "input"))
      (node (ref "IC11") (pin "4") (pinfunction "-VS_4") (pintype "input"))
      (node (ref "IC2") (pin "4") (pinfunction "-VS_4") (pintype "input"))
      (node (ref "IC3") (pin "5") (pinfunction "-VS_5") (pintype "bidirectional"))
      (node (ref "IC4") (pin "5") (pinfunction "-VS_5") (pintype "bidirectional"))
      (node (ref "IC5") (pin "4") (pinfunction "-VS_4") (pintype "input"))
      (node (ref "IC6") (pin "4") (pinfunction "-VS_4") (pintype "input"))
      (node (ref "IC7") (pin "4") (pinfunction "-VS_4") (pintype "input"))
      (node (ref "IC8") (pin "4") (pinfunction "-VS_4") (pintype "input"))
      (node (ref "IC9") (pin "4") (pinfunction "-VS_4") (pintype "input"))
      (node (ref "R37") (pin "1") (pinfunction "1_1") (pintype "passive"))
      (node (ref "U1") (pin "4") (pinfunction "V-_4") (pintype "power_in"))
      (node (ref "X7") (pin "3") (pinfunction "S_3") (pintype "passive"))
    )
    (net (code "44") (name "VERROR") (class "Default")
      (node (ref "IC2") (pin "3") (pinfunction "IN+_3") (pintype "input"))
      (node (ref "R15") (pin "2") (pinfunction "2_2") (pintype "passive"))
      (node (ref "R16") (pin "2") (pinfunction "2_2") (pintype "passive"))
      (node (ref "R18") (pin "2") (pinfunction "2_2") (pintype "passive"))
      (node (ref "U1") (pin "5") (pinfunction "SENSE_5") (pintype "passive"))
      (node (ref "U1") (pin "6") (pinfunction "OUT_6") (pintype "output"))
    )
    (net (code "45") (name "VN") (class "Default")
      (node (ref "IC10") (pin "2") (pinfunction "IN-_2") (pintype "input"))
      (node (ref "IC10") (pin "6") (pinfunction "OUT_6") (pintype "output"))
      (node (ref "R22") (pin "2") (pinfunction "2_2") (pintype "passive"))
    )
    (net (code "46") (name "VP") (class "Default")
      (node (ref "IC11") (pin "2") (pinfunction "IN-_2") (pintype "input"))
      (node (ref "IC11") (pin "6") (pinfunction "OUT_6") (pintype "output"))
      (node (ref "R25") (pin "1") (pinfunction "1_1") (pintype "passive"))
    )
  )
)
